# Bluetooth.net
KiCad netlist of a schematic drawn in Altium Designer
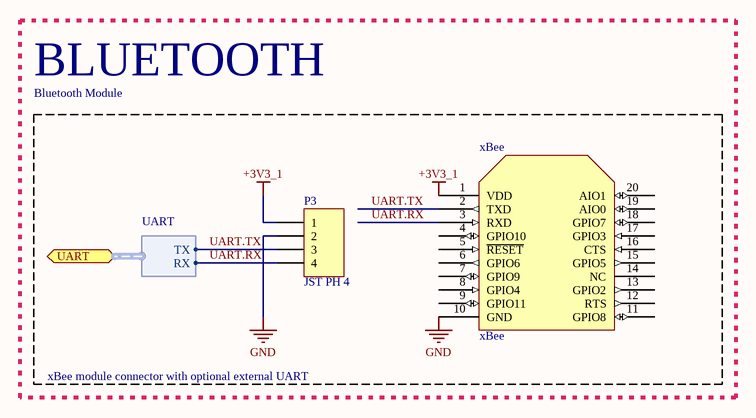
[diagram p0: Bluetooth.SchDoc]

(export (version "E")
  (design (tool "Eeschema 10.0.6"))
  (components
    (comp (ref "P3")
      (value "JST PH 4")
      (footprint "B4B-PH-K")
      (libsource (lib "CustomLibrary") (part "JST PH 4"))
    )
    (comp (ref "xBee") (value "xBee") (footprint "xBee") (libsource (lib "CustomLibrary") (part "xBee")))
  )
  (nets
    (net (code "2") (name "+3V3_1") (class "Default")
      (node (ref "P3") (pin "1") (pinfunction "1_1") (pintype "passive"))
      (node (ref "xBee") (pin "1") (pinfunction "VDD_1") (pintype "power_in"))
    )
    (net (code "3") (name "/UART.RX") (class "Default")
      (node (ref "P3") (pin "4") (pinfunction "4_4") (pintype "passive"))
      (node (ref "xBee") (pin "3") (pinfunction "RXD_3") (pintype "input"))
    )
    (net (code "4") (name "/UART.TX") (class "Default")
      (node (ref "P3") (pin "3") (pinfunction "3_3") (pintype "passive"))
      (node (ref "xBee") (pin "2") (pinfunction "TXD_2") (pintype "output"))
    )
    (net (code "6") (name "GND") (class "Default")
      (node (ref "P3") (pin "2") (pinfunction "2_2") (pintype "passive"))
      (node (ref "xBee") (pin "10") (pinfunction "GND_10") (pintype "power_in"))
    )
    (net (code "7") (name "unconnected-(xBee-AIO0-Pad19)") (class "Default")
      (node (ref "xBee") (pin "19") (pinfunction "AIO0_19") (pintype "bidirectional"))
    )
    (net (code "8") (name "unconnected-(xBee-AIO1-Pad20)") (class "Default")
      (node (ref "xBee") (pin "20") (pinfunction "AIO1_20") (pintype "bidirectional"))
    )
    (net (code "9") (name "unconnected-(xBee-CTS-Pad16)") (class "Default")
      (node (ref "xBee") (pin "16") (pinfunction "CTS_16") (pintype "input"))
    )
    (net (code "10") (name "unconnected-(xBee-GPIO2-Pad13)") (class "Default")
      (node (ref "xBee") (pin "13") (pinfunction "GPIO2_13") (pintype "output"))
    )
    (net (code "11") (name "unconnected-(xBee-GPIO3-Pad17)") (class "Default")
      (node (ref "xBee") (pin "17") (pinfunction "GPIO3_17") (pintype "input"))
    )
    (net (code "12") (name "unconnected-(xBee-GPIO4-Pad8)") (class "Default")
      (node (ref "xBee") (pin "8") (pinfunction "GPIO4_8") (pintype "input"))
    )
    (net (code "13") (name "unconnected-(xBee-GPIO5-Pad15)") (class "Default")
      (node (ref "xBee") (pin "15") (pinfunction "GPIO5_15") (pintype "output"))
    )
    (net (code "14") (name "unconnected-(xBee-GPIO6-Pad6)") (class "Default")
      (node (ref "xBee") (pin "6") (pinfunction "GPIO6_6") (pintype "output"))
    )
    (net (code "15") (name "unconnected-(xBee-GPIO7-Pad18)") (class "Default")
      (node (ref "xBee") (pin "18") (pinfunction "GPIO7_18") (pintype "bidirectional"))
    )
    (net (code "16") (name "unconnected-(xBee-GPIO8-Pad11)") (class "Default")
      (node (ref "xBee") (pin "11") (pinfunction "GPIO8_11") (pintype "bidirectional"))
    )
    (net (code "17") (name "unconnected-(xBee-GPIO9-Pad7)") (class "Default")
      (node (ref "xBee") (pin "7") (pinfunction "GPIO9_7") (pintype "bidirectional"))
    )
    (net (code "18") (name "unconnected-(xBee-GPIO10-Pad4)") (class "Default")
      (node (ref "xBee") (pin "4") (pinfunction "GPIO10_4") (pintype "bidirectional"))
    )
    (net (code "19") (name "unconnected-(xBee-GPIO11-Pad9)") (class "Default")
      (node (ref "xBee") (pin "9") (pinfunction "GPIO11_9") (pintype "bidirectional"))
    )
    (net (code "20") (name "unconnected-(xBee-NC-Pad14)") (class "Default")
      (node (ref "xBee") (pin "14") (pinfunction "NC_14") (pintype "passive"))
    )
    (net (code "21") (name "unconnected-(xBee-RTS-Pad12)") (class "Default")
      (node (ref "xBee") (pin "12") (pinfunction "RTS_12") (pintype "output"))
    )
    (net (code "22") (name "unconnected-(xBee-~{RESET}-Pad5)") (class "Default")
      (node (ref "xBee") (pin "5") (pinfunction "~{RESET}_5") (pintype "input"))
    )
  )
)
